# PineWoodDerby-Mega_Shield.net
KiCad netlist of a schematic drawn in EAGLE
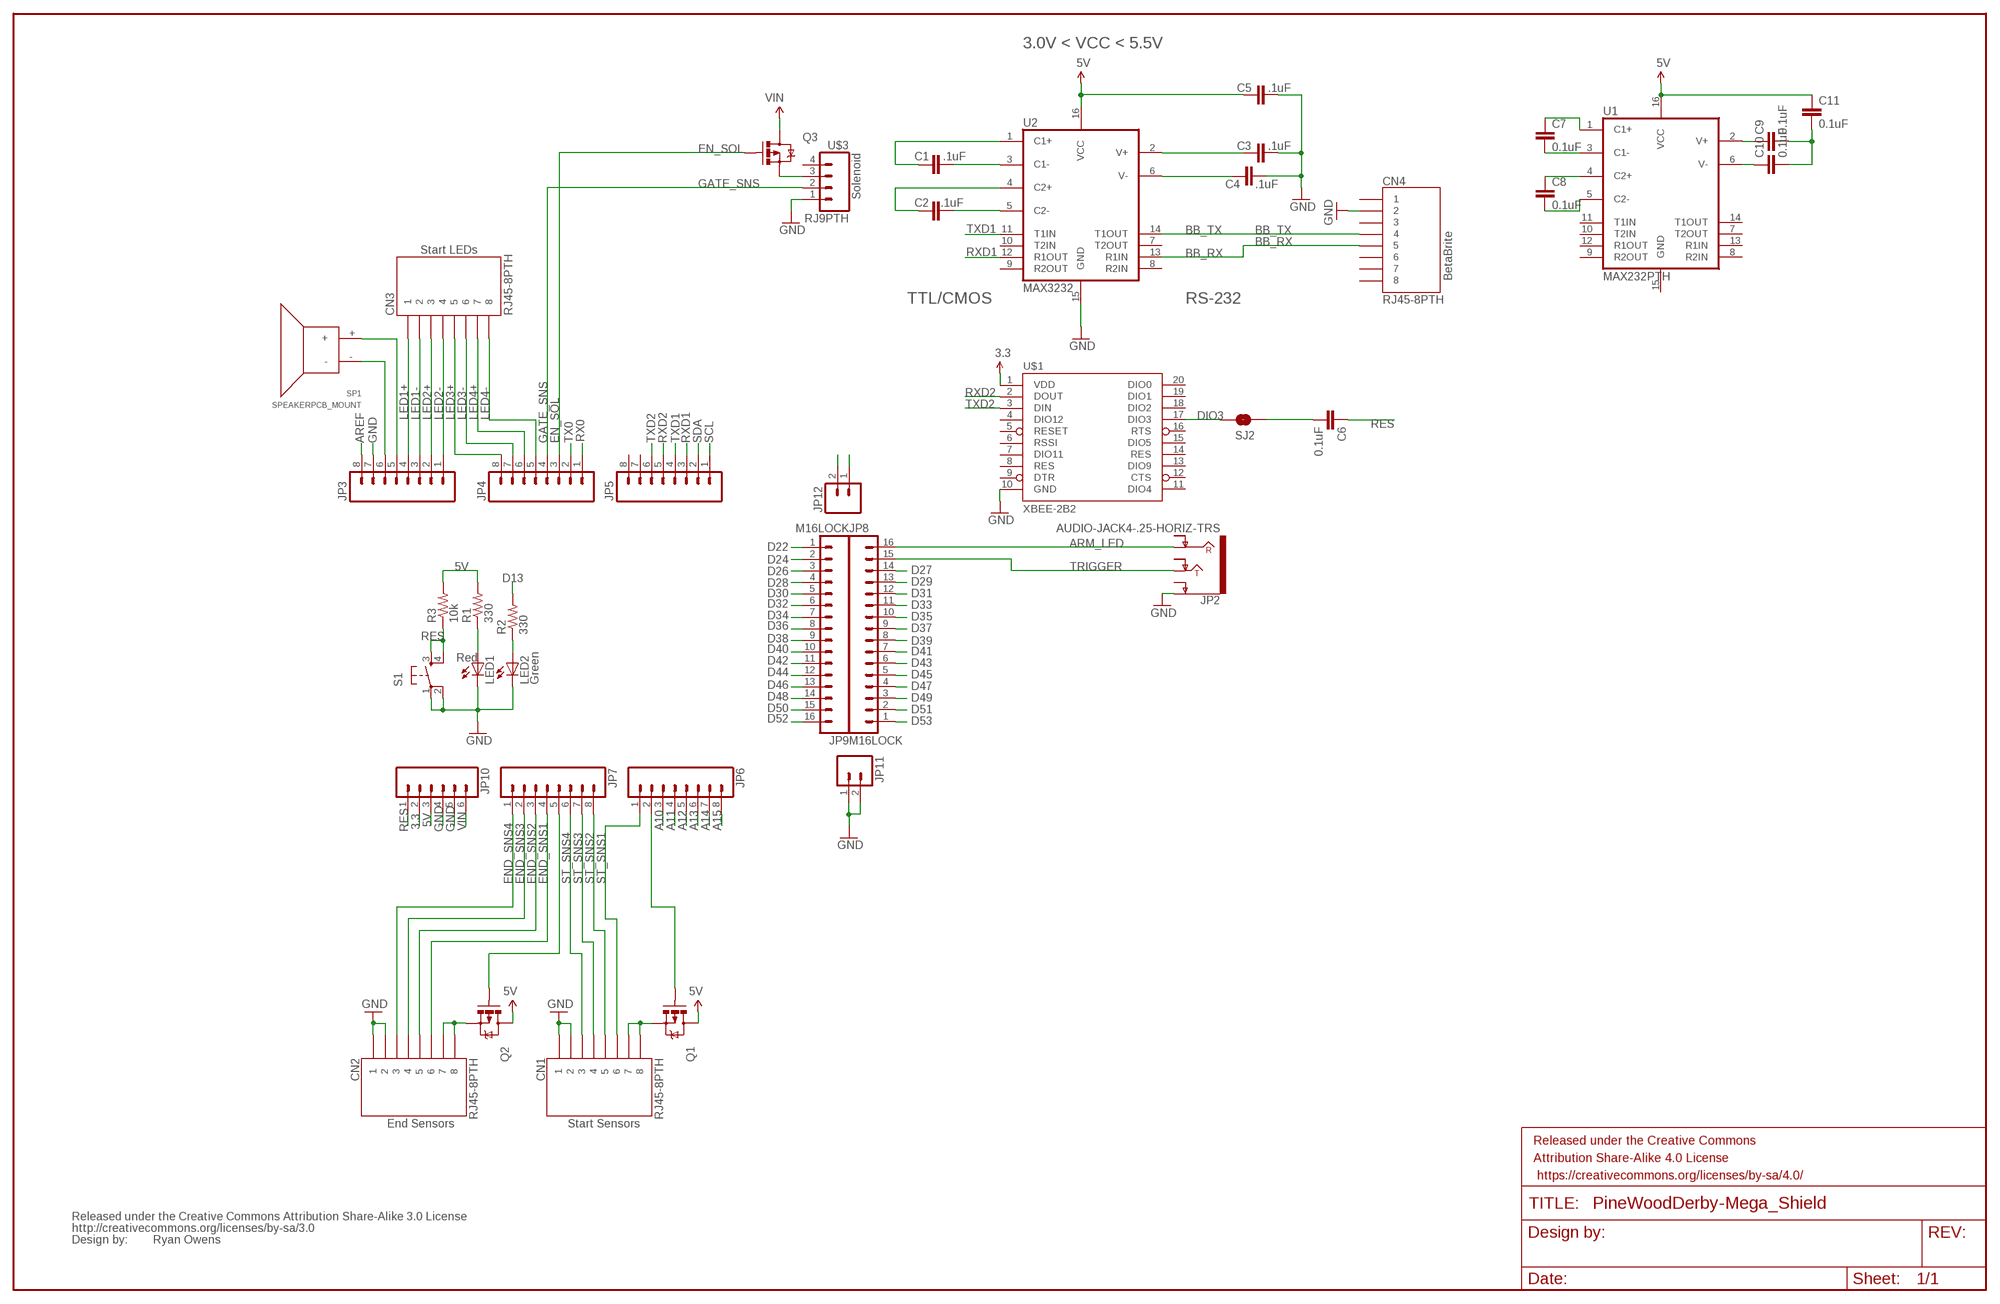
[diagram p0: schematic, sheet 1]

(export (version "E")
  (design (tool "Eeschema 10.0.6"))
  (components
    (comp (ref "C1")
      (value ".1uF")
      (footprint "eagle-import:0402-CAP")
      (libsource (lib "eagle-import") (part "SparkFun-Passives_CAP0402-CAP"))
    )
    (comp (ref "C2")
      (value ".1uF")
      (footprint "eagle-import:0402-CAP")
      (libsource (lib "eagle-import") (part "SparkFun-Passives_CAP0402-CAP"))
    )
    (comp (ref "C3")
      (value ".1uF")
      (footprint "eagle-import:0402-CAP")
      (libsource (lib "eagle-import") (part "SparkFun-Passives_CAP0402-CAP"))
    )
    (comp (ref "C4")
      (value ".1uF")
      (footprint "eagle-import:0402-CAP")
      (libsource (lib "eagle-import") (part "SparkFun-Passives_CAP0402-CAP"))
    )
    (comp (ref "C5")
      (value ".1uF")
      (footprint "eagle-import:0402-CAP")
      (libsource (lib "eagle-import") (part "SparkFun-Passives_CAP0402-CAP"))
    )
    (comp (ref "C6")
      (value "0.1uF")
      (footprint "eagle-import:0402-CAP")
      (libsource (lib "eagle-import") (part "CAP0402-CAP"))
    )
    (comp (ref "C7")
      (value "0.1uF")
      (footprint "eagle-import:CAP-PTH-SMALL-KIT")
      (libsource (lib "eagle-import") (part "0.1UF-50V-20%(PTH)KIT-EZ"))
    )
    (comp (ref "C8")
      (value "0.1uF")
      (footprint "eagle-import:CAP-PTH-SMALL-KIT")
      (libsource (lib "eagle-import") (part "0.1UF-50V-20%(PTH)KIT-EZ"))
    )
    (comp (ref "C9")
      (value "0.1uF")
      (footprint "eagle-import:CAP-PTH-SMALL-KIT")
      (libsource (lib "eagle-import") (part "0.1UF-50V-20%(PTH)KIT-EZ"))
    )
    (comp (ref "C10")
      (value "0.1uF")
      (footprint "eagle-import:CAP-PTH-SMALL-KIT")
      (libsource (lib "eagle-import") (part "0.1UF-50V-20%(PTH)KIT-EZ"))
    )
    (comp (ref "C11")
      (value "0.1uF")
      (footprint "eagle-import:CAP-PTH-SMALL-KIT")
      (libsource (lib "eagle-import") (part "0.1UF-50V-20%(PTH)KIT-EZ"))
    )
    (comp (ref "CN1")
      (value "RJ45-8PTH")
      (footprint "eagle-import:RJ45-8")
      (fields (field (name "LABEL") "Start Sensors"))
      (libsource (lib "eagle-import") (part "RJ45-8PTH"))
    )
    (comp (ref "CN2")
      (value "RJ45-8PTH")
      (footprint "eagle-import:RJ45-8")
      (fields (field (name "LABEL") "End Sensors"))
      (libsource (lib "eagle-import") (part "RJ45-8PTH"))
    )
    (comp (ref "CN3")
      (value "RJ45-8PTH")
      (footprint "eagle-import:RJ45-8")
      (fields (field (name "LABEL") "Start LEDs"))
      (libsource (lib "eagle-import") (part "RJ45-8PTH"))
    )
    (comp (ref "CN4")
      (value "RJ45-8PTH")
      (footprint "eagle-import:RJ45-8")
      (fields (field (name "LABEL") "BetaBrite"))
      (libsource (lib "eagle-import") (part "RJ45-8PTH"))
    )
    (comp (ref "FRAME2")
      (value "FRAME-LEDGER")
      (footprint "eagle-import:CREATIVE_COMMONS")
      (libsource (lib "eagle-import") (part "FRAME-LEDGER"))
    )
    (comp (ref "JP2")
      (value "AUDIO-JACK4-.25-HORIZ-TRS")
      (footprint "eagle-import:AUDIO-JACK-.25-INCH-HORIZ-PTH")
      (libsource (lib "eagle-import") (part "AUDIO-JACK4-.25-HORIZ-TRS"))
    )
    (comp (ref "JP3")
      (value "M08LOCK")
      (footprint "eagle-import:1X08_LOCK")
      (libsource (lib "eagle-import") (part "M08LOCK"))
    )
    (comp (ref "JP4")
      (value "M08LOCK")
      (footprint "eagle-import:1X08_LOCK")
      (libsource (lib "eagle-import") (part "M08LOCK"))
    )
    (comp (ref "JP5")
      (value "M08LOCK")
      (footprint "eagle-import:1X08_LOCK")
      (libsource (lib "eagle-import") (part "M08LOCK"))
    )
    (comp (ref "JP6")
      (value "M08LOCK")
      (footprint "eagle-import:1X08_LOCK")
      (libsource (lib "eagle-import") (part "M08LOCK"))
    )
    (comp (ref "JP7")
      (value "M08LOCK")
      (footprint "eagle-import:1X08_LOCK")
      (libsource (lib "eagle-import") (part "M08LOCK"))
    )
    (comp (ref "JP8")
      (value "M16LOCK")
      (footprint "eagle-import:1X16_LOCK")
      (libsource (lib "eagle-import") (part "M16LOCK"))
    )
    (comp (ref "JP9")
      (value "M16LOCK")
      (footprint "eagle-import:1X16_LOCK")
      (libsource (lib "eagle-import") (part "M16LOCK"))
    )
    (comp (ref "JP10")
      (value "M06LOCK")
      (footprint "eagle-import:1X06_LOCK")
      (libsource (lib "eagle-import") (part "M06LOCK"))
    )
    (comp (ref "JP11")
      (value "M02LOCK")
      (footprint "eagle-import:1X02_LOCK")
      (libsource (lib "eagle-import") (part "M02LOCK"))
    )
    (comp (ref "JP12")
      (value "M02LOCK")
      (footprint "eagle-import:1X02_LOCK")
      (libsource (lib "eagle-import") (part "M02LOCK"))
    )
    (comp (ref "LED1")
      (value "Red")
      (footprint "eagle-import:LED5MM")
      (libsource (lib "eagle-import") (part "LED5MM"))
    )
    (comp (ref "LED2")
      (value "Green")
      (footprint "eagle-import:LED5MM")
      (libsource (lib "eagle-import") (part "LED5MM"))
    )
    (comp (ref "Q1")
      (value "MOSFET-PCHANNELFQP27P06")
      (footprint "eagle-import:TO220V")
      (libsource (lib "eagle-import") (part "MOSFET-PCHANNELFQP27P06"))
    )
    (comp (ref "Q2")
      (value "MOSFET-PCHANNELFQP27P06")
      (footprint "eagle-import:TO220V")
      (libsource (lib "eagle-import") (part "MOSFET-PCHANNELFQP27P06"))
    )
    (comp (ref "Q3")
      (value "MOSFET-PCHANNELFQP27P06")
      (footprint "eagle-import:TO220V")
      (libsource (lib "eagle-import") (part "MOSFET-PCHANNELFQP27P06"))
    )
    (comp (ref "R1")
      (value "330")
      (footprint "eagle-import:AXIAL-0.3")
      (libsource (lib "eagle-import") (part "RESISTORPTH1"))
    )
    (comp (ref "R2")
      (value "330")
      (footprint "eagle-import:AXIAL-0.3")
      (libsource (lib "eagle-import") (part "RESISTORPTH1"))
    )
    (comp (ref "R3")
      (value "10k")
      (footprint "eagle-import:AXIAL-0.3")
      (libsource (lib "eagle-import") (part "RESISTORPTH1"))
    )
    (comp (ref "S1")
      (value "TAC_SWITCHPTH")
      (footprint "eagle-import:TACTILE-PTH")
      (libsource (lib "eagle-import") (part "TAC_SWITCHPTH"))
    )
    (comp (ref "SJ2")
      (value "SOLDERJUMPERTRACE")
      (footprint "eagle-import:SJ_2S-TRACE")
      (libsource (lib "eagle-import") (part "SOLDERJUMPERTRACE"))
    )
    (comp (ref "SP1")
      (value "SPEAKERPCB_MOUNT")
      (footprint "eagle-import:PCB_MOUNT_SPEAKER")
      (fields (field (name "MFG") "SANCO"))
      (libsource (lib "eagle-import") (part "SPEAKERPCB_MOUNT"))
    )
    (comp (ref "U$1")
      (value "XBEE-2B2")
      (footprint "eagle-import:XBEE-SILK")
      (libsource (lib "eagle-import") (part "XBEE-2B2"))
    )
    (comp (ref "U$2")
      (value "CREATIVE_COMMONS")
      (footprint "eagle-import:CREATIVE_COMMONS")
      (libsource (lib "eagle-import") (part "CREATIVE_COMMONS"))
    )
    (comp (ref "U$3")
      (value "RJ9PTH")
      (footprint "eagle-import:RJ9")
      (fields (field (name "LABEL") "Solenoid"))
      (libsource (lib "eagle-import") (part "RJ9PTH"))
    )
    (comp (ref "U1")
      (value "MAX232PTH")
      (footprint "eagle-import:DIL16")
      (libsource (lib "eagle-import") (part "MAX232PTH"))
    )
    (comp (ref "U2")
      (value "MAX3232")
      (footprint "eagle-import:SO016")
      (fields (field (name "PROD_ID") "IC-08171"))
      (libsource (lib "eagle-import") (part "MAX232SOIC16"))
    )
  )
  (nets
    (net (code "1") (name "/5V@1") (class "Default")
      (node (ref "JP12") (pin "1") (pinfunction "1_1") (pintype "passive"))
      (node (ref "JP12") (pin "2") (pinfunction "2_2") (pintype "passive"))
    )
    (net (code "2") (name "/A10") (class "Default")
      (node (ref "JP6") (pin "3") (pinfunction "3_3") (pintype "passive"))
    )
    (net (code "3") (name "/A11") (class "Default")
      (node (ref "JP6") (pin "4") (pinfunction "4_4") (pintype "passive"))
    )
    (net (code "4") (name "/A12") (class "Default")
      (node (ref "JP6") (pin "5") (pinfunction "5_5") (pintype "passive"))
    )
    (net (code "5") (name "/A13") (class "Default")
      (node (ref "JP6") (pin "6") (pinfunction "6_6") (pintype "passive"))
    )
    (net (code "6") (name "/A14") (class "Default")
      (node (ref "JP6") (pin "7") (pinfunction "7_7") (pintype "passive"))
    )
    (net (code "7") (name "/A15") (class "Default")
      (node (ref "JP6") (pin "8") (pinfunction "8_8") (pintype "passive"))
    )
    (net (code "8") (name "/AREF") (class "Default")
      (node (ref "JP3") (pin "8") (pinfunction "8_8") (pintype "passive"))
    )
    (net (code "9") (name "/ARM_LED") (class "Default")
      (node (ref "JP2") (pin "RING") (pinfunction "RING_RING") (pintype "bidirectional"))
      (node (ref "JP8") (pin "16") (pinfunction "16_16") (pintype "passive"))
    )
    (net (code "10") (name "/BB_RX") (class "Default")
      (node (ref "CN4") (pin "5") (pinfunction "5_5") (pintype "bidirectional"))
      (node (ref "U2") (pin "13") (pinfunction "R1IN_13") (pintype "input"))
    )
    (net (code "11") (name "/BB_TX") (class "Default")
      (node (ref "CN4") (pin "4") (pinfunction "4_4") (pintype "bidirectional"))
      (node (ref "U2") (pin "14") (pinfunction "T1OUT_14") (pintype "output"))
    )
    (net (code "12") (name "/D13") (class "Default")
      (node (ref "R2") (pin "P$2") (pinfunction "2_P$2") (pintype "passive"))
    )
    (net (code "13") (name "/D22") (class "Default")
      (node (ref "JP9") (pin "1") (pinfunction "1_1") (pintype "passive"))
    )
    (net (code "14") (name "/D24") (class "Default")
      (node (ref "JP9") (pin "2") (pinfunction "2_2") (pintype "passive"))
    )
    (net (code "15") (name "/D26") (class "Default")
      (node (ref "JP9") (pin "3") (pinfunction "3_3") (pintype "passive"))
    )
    (net (code "16") (name "/D27") (class "Default")
      (node (ref "JP8") (pin "14") (pinfunction "14_14") (pintype "passive"))
    )
    (net (code "17") (name "/D28") (class "Default")
      (node (ref "JP9") (pin "4") (pinfunction "4_4") (pintype "passive"))
    )
    (net (code "18") (name "/D29") (class "Default")
      (node (ref "JP8") (pin "13") (pinfunction "13_13") (pintype "passive"))
    )
    (net (code "19") (name "/D30") (class "Default")
      (node (ref "JP9") (pin "5") (pinfunction "5_5") (pintype "passive"))
    )
    (net (code "20") (name "/D31") (class "Default")
      (node (ref "JP8") (pin "12") (pinfunction "12_12") (pintype "passive"))
    )
    (net (code "21") (name "/D32") (class "Default")
      (node (ref "JP9") (pin "6") (pinfunction "6_6") (pintype "passive"))
    )
    (net (code "22") (name "/D33") (class "Default")
      (node (ref "JP8") (pin "11") (pinfunction "11_11") (pintype "passive"))
    )
    (net (code "23") (name "/D34") (class "Default")
      (node (ref "JP9") (pin "7") (pinfunction "7_7") (pintype "passive"))
    )
    (net (code "24") (name "/D35") (class "Default")
      (node (ref "JP8") (pin "10") (pinfunction "10_10") (pintype "passive"))
    )
    (net (code "25") (name "/D36") (class "Default")
      (node (ref "JP9") (pin "8") (pinfunction "8_8") (pintype "passive"))
    )
    (net (code "26") (name "/D37") (class "Default")
      (node (ref "JP8") (pin "9") (pinfunction "9_9") (pintype "passive"))
    )
    (net (code "27") (name "/D38") (class "Default")
      (node (ref "JP9") (pin "9") (pinfunction "9_9") (pintype "passive"))
    )
    (net (code "28") (name "/D39") (class "Default")
      (node (ref "JP8") (pin "8") (pinfunction "8_8") (pintype "passive"))
    )
    (net (code "29") (name "/D40") (class "Default")
      (node (ref "JP9") (pin "10") (pinfunction "10_10") (pintype "passive"))
    )
    (net (code "30") (name "/D41") (class "Default")
      (node (ref "JP8") (pin "7") (pinfunction "7_7") (pintype "passive"))
    )
    (net (code "31") (name "/D42") (class "Default")
      (node (ref "JP9") (pin "11") (pinfunction "11_11") (pintype "passive"))
    )
    (net (code "32") (name "/D43") (class "Default")
      (node (ref "JP8") (pin "6") (pinfunction "6_6") (pintype "passive"))
    )
    (net (code "33") (name "/D44") (class "Default")
      (node (ref "JP9") (pin "12") (pinfunction "12_12") (pintype "passive"))
    )
    (net (code "34") (name "/D45") (class "Default")
      (node (ref "JP8") (pin "5") (pinfunction "5_5") (pintype "passive"))
    )
    (net (code "35") (name "/D46") (class "Default")
      (node (ref "JP9") (pin "13") (pinfunction "13_13") (pintype "passive"))
    )
    (net (code "36") (name "/D47") (class "Default")
      (node (ref "JP8") (pin "4") (pinfunction "4_4") (pintype "passive"))
    )
    (net (code "37") (name "/D48") (class "Default")
      (node (ref "JP9") (pin "14") (pinfunction "14_14") (pintype "passive"))
    )
    (net (code "38") (name "/D49") (class "Default")
      (node (ref "JP8") (pin "3") (pinfunction "3_3") (pintype "passive"))
    )
    (net (code "39") (name "/D50") (class "Default")
      (node (ref "JP9") (pin "15") (pinfunction "15_15") (pintype "passive"))
    )
    (net (code "40") (name "/D51") (class "Default")
      (node (ref "JP8") (pin "2") (pinfunction "2_2") (pintype "passive"))
    )
    (net (code "41") (name "/D52") (class "Default")
      (node (ref "JP9") (pin "16") (pinfunction "16_16") (pintype "passive"))
    )
    (net (code "42") (name "/D53") (class "Default")
      (node (ref "JP8") (pin "1") (pinfunction "1_1") (pintype "passive"))
    )
    (net (code "43") (name "/DIO3") (class "Default")
      (node (ref "SJ2") (pin "2") (pinfunction "2_2") (pintype "passive"))
      (node (ref "U$1") (pin "17") (pinfunction "DIO3_17") (pintype "bidirectional"))
    )
    (net (code "44") (name "/END_SNS1") (class "Default")
      (node (ref "CN2") (pin "6") (pinfunction "6_6") (pintype "bidirectional"))
      (node (ref "JP7") (pin "4") (pinfunction "4_4") (pintype "passive"))
    )
    (net (code "45") (name "/END_SNS2") (class "Default")
      (node (ref "CN2") (pin "5") (pinfunction "5_5") (pintype "bidirectional"))
      (node (ref "JP7") (pin "3") (pinfunction "3_3") (pintype "passive"))
    )
    (net (code "46") (name "/END_SNS3") (class "Default")
      (node (ref "CN2") (pin "4") (pinfunction "4_4") (pintype "bidirectional"))
      (node (ref "JP7") (pin "2") (pinfunction "2_2") (pintype "passive"))
    )
    (net (code "47") (name "/END_SNS4") (class "Default")
      (node (ref "CN2") (pin "3") (pinfunction "3_3") (pintype "bidirectional"))
      (node (ref "JP7") (pin "1") (pinfunction "1_1") (pintype "passive"))
    )
    (net (code "48") (name "/EN_SOL") (class "Default")
      (node (ref "JP4") (pin "3") (pinfunction "3_3") (pintype "passive"))
      (node (ref "Q3") (pin "1") (pinfunction "G_1") (pintype "passive"))
    )
    (net (code "49") (name "/GATE_SNS") (class "Default")
      (node (ref "JP4") (pin "4") (pinfunction "4_4") (pintype "passive"))
      (node (ref "U$3") (pin "2") (pinfunction "2_2") (pintype "passive"))
    )
    (net (code "50") (name "/LED1+") (class "Default")
      (node (ref "CN3") (pin "1") (pinfunction "1_1") (pintype "bidirectional"))
      (node (ref "JP3") (pin "4") (pinfunction "4_4") (pintype "passive"))
    )
    (net (code "51") (name "/LED1-") (class "Default")
      (node (ref "CN3") (pin "2") (pinfunction "2_2") (pintype "bidirectional"))
      (node (ref "JP3") (pin "3") (pinfunction "3_3") (pintype "passive"))
    )
    (net (code "52") (name "/LED2+") (class "Default")
      (node (ref "CN3") (pin "3") (pinfunction "3_3") (pintype "bidirectional"))
      (node (ref "JP3") (pin "2") (pinfunction "2_2") (pintype "passive"))
    )
    (net (code "53") (name "/LED2-") (class "Default")
      (node (ref "CN3") (pin "4") (pinfunction "4_4") (pintype "bidirectional"))
      (node (ref "JP3") (pin "1") (pinfunction "1_1") (pintype "passive"))
    )
    (net (code "54") (name "/LED3+") (class "Default")
      (node (ref "CN3") (pin "5") (pinfunction "5_5") (pintype "bidirectional"))
      (node (ref "JP4") (pin "8") (pinfunction "8_8") (pintype "passive"))
    )
    (net (code "55") (name "/LED3-") (class "Default")
      (node (ref "CN3") (pin "6") (pinfunction "6_6") (pintype "bidirectional"))
      (node (ref "JP4") (pin "7") (pinfunction "7_7") (pintype "passive"))
    )
    (net (code "56") (name "/LED4+") (class "Default")
      (node (ref "CN3") (pin "7") (pinfunction "7_7") (pintype "bidirectional"))
      (node (ref "JP4") (pin "6") (pinfunction "6_6") (pintype "passive"))
    )
    (net (code "57") (name "/LED4-") (class "Default")
      (node (ref "CN3") (pin "8") (pinfunction "8_8") (pintype "bidirectional"))
      (node (ref "JP4") (pin "5") (pinfunction "5_5") (pintype "passive"))
    )
    (net (code "58") (name "/RES") (class "Default")
      (node (ref "C6") (pin "1") (pinfunction "1_1") (pintype "passive"))
      (node (ref "JP10") (pin "1") (pinfunction "1_1") (pintype "passive"))
      (node (ref "R3") (pin "P$1") (pinfunction "1_P$1") (pintype "passive"))
      (node (ref "S1") (pin "3") (pinfunction "3_3") (pintype "passive"))
      (node (ref "S1") (pin "4") (pinfunction "4_4") (pintype "passive"))
    )
    (net (code "59") (name "/RX0") (class "Default")
      (node (ref "JP4") (pin "1") (pinfunction "1_1") (pintype "passive"))
    )
    (net (code "60") (name "/RXD1") (class "Default")
      (node (ref "JP5") (pin "3") (pinfunction "3_3") (pintype "passive"))
      (node (ref "U2") (pin "12") (pinfunction "R1OUT_12") (pintype "output"))
    )
    (net (code "61") (name "/RXD2") (class "Default")
      (node (ref "JP5") (pin "5") (pinfunction "5_5") (pintype "passive"))
      (node (ref "U$1") (pin "2") (pinfunction "DOUT_2") (pintype "output"))
    )
    (net (code "62") (name "/SCL") (class "Default")
      (node (ref "JP5") (pin "1") (pinfunction "1_1") (pintype "passive"))
    )
    (net (code "63") (name "/SDA") (class "Default")
      (node (ref "JP5") (pin "2") (pinfunction "2_2") (pintype "passive"))
    )
    (net (code "64") (name "/ST_SNS1") (class "Default")
      (node (ref "CN1") (pin "6") (pinfunction "6_6") (pintype "bidirectional"))
      (node (ref "JP6") (pin "1") (pinfunction "1_1") (pintype "passive"))
    )
    (net (code "65") (name "/ST_SNS2") (class "Default")
      (node (ref "CN1") (pin "5") (pinfunction "5_5") (pintype "bidirectional"))
      (node (ref "JP7") (pin "8") (pinfunction "8_8") (pintype "passive"))
    )
    (net (code "66") (name "/ST_SNS3") (class "Default")
      (node (ref "CN1") (pin "4") (pinfunction "4_4") (pintype "bidirectional"))
      (node (ref "JP7") (pin "7") (pinfunction "7_7") (pintype "passive"))
    )
    (net (code "67") (name "/ST_SNS4") (class "Default")
      (node (ref "CN1") (pin "3") (pinfunction "3_3") (pintype "bidirectional"))
      (node (ref "JP7") (pin "6") (pinfunction "6_6") (pintype "passive"))
    )
    (net (code "68") (name "/TRIGGER") (class "Default")
      (node (ref "JP2") (pin "TIP") (pinfunction "TIP_TIP") (pintype "bidirectional"))
      (node (ref "JP8") (pin "15") (pinfunction "15_15") (pintype "passive"))
    )
    (net (code "69") (name "/TX0") (class "Default")
      (node (ref "JP4") (pin "2") (pinfunction "2_2") (pintype "passive"))
    )
    (net (code "70") (name "/TXD1") (class "Default")
      (node (ref "JP5") (pin "4") (pinfunction "4_4") (pintype "passive"))
      (node (ref "U2") (pin "11") (pinfunction "T1IN_11") (pintype "input"))
    )
    (net (code "71") (name "/TXD2") (class "Default")
      (node (ref "JP5") (pin "6") (pinfunction "6_6") (pintype "passive"))
      (node (ref "U$1") (pin "3") (pinfunction "DIN_3") (pintype "input"))
    )
    (net (code "72") (name "3.3") (class "Default")
      (node (ref "JP10") (pin "2") (pinfunction "2_2") (pintype "passive"))
      (node (ref "U$1") (pin "1") (pinfunction "VDD_1") (pintype "power_in"))
    )
    (net (code "73") (name "5V") (class "Default")
      (node (ref "C11") (pin "1") (pinfunction "1_1") (pintype "passive"))
      (node (ref "C5") (pin "1") (pinfunction "1_1") (pintype "passive"))
      (node (ref "JP10") (pin "3") (pinfunction "3_3") (pintype "passive"))
      (node (ref "Q1") (pin "2") (pinfunction "D_2") (pintype "passive"))
      (node (ref "Q2") (pin "2") (pinfunction "D_2") (pintype "passive"))
      (node (ref "R1") (pin "P$2") (pinfunction "2_P$2") (pintype "passive"))
      (node (ref "R3") (pin "P$2") (pinfunction "2_P$2") (pintype "passive"))
      (node (ref "U1") (pin "16") (pinfunction "VCC_16") (pintype "bidirectional"))
      (node (ref "U2") (pin "16") (pinfunction "VCC_16") (pintype "bidirectional"))
    )
    (net (code "74") (name "GND") (class "Default")
      (node (ref "C3") (pin "2") (pinfunction "2_2") (pintype "passive"))
      (node (ref "C4") (pin "2") (pinfunction "2_2") (pintype "passive"))
      (node (ref "C5") (pin "2") (pinfunction "2_2") (pintype "passive"))
      (node (ref "CN1") (pin "1") (pinfunction "1_1") (pintype "bidirectional"))
      (node (ref "CN1") (pin "2") (pinfunction "2_2") (pintype "bidirectional"))
      (node (ref "CN2") (pin "1") (pinfunction "1_1") (pintype "bidirectional"))
      (node (ref "CN2") (pin "2") (pinfunction "2_2") (pintype "bidirectional"))
      (node (ref "CN4") (pin "2") (pinfunction "2_2") (pintype "bidirectional"))
      (node (ref "JP10") (pin "4") (pinfunction "4_4") (pintype "passive"))
      (node (ref "JP10") (pin "5") (pinfunction "5_5") (pintype "passive"))
      (node (ref "JP11") (pin "1") (pinfunction "1_1") (pintype "passive"))
      (node (ref "JP11") (pin "2") (pinfunction "2_2") (pintype "passive"))
      (node (ref "JP2") (pin "SLEEVE") (pinfunction "EARTH_SLEEVE") (pintype "bidirectional"))
      (node (ref "JP3") (pin "7") (pinfunction "7_7") (pintype "passive"))
      (node (ref "LED1") (pin "K") (pinfunction "C_K") (pintype "passive"))
      (node (ref "LED2") (pin "K") (pinfunction "C_K") (pintype "passive"))
      (node (ref "S1") (pin "1") (pinfunction "1_1") (pintype "passive"))
      (node (ref "S1") (pin "2") (pinfunction "2_2") (pintype "passive"))
      (node (ref "U$1") (pin "10") (pinfunction "GND_10") (pintype "power_in"))
      (node (ref "U$3") (pin "1") (pinfunction "1_1") (pintype "passive"))
      (node (ref "U2") (pin "15") (pinfunction "GND_15") (pintype "bidirectional"))
    )
    (net (code "75") (name "Net-(C6-Pad2)") (class "Default")
      (node (ref "C6") (pin "2") (pinfunction "2_2") (pintype "passive"))
      (node (ref "SJ2") (pin "1") (pinfunction "1_1") (pintype "passive"))
    )
    (net (code "76") (name "Net-(C10-Pad2)") (class "Default")
      (node (ref "C10") (pin "2") (pinfunction "2_2") (pintype "passive"))
      (node (ref "C11") (pin "2") (pinfunction "2_2") (pintype "passive"))
      (node (ref "C9") (pin "2") (pinfunction "2_2") (pintype "passive"))
    )
    (net (code "77") (name "Net-(JP3-Pad5)") (class "Default")
      (node (ref "JP3") (pin "5") (pinfunction "5_5") (pintype "passive"))
      (node (ref "SP1") (pin "+") (pinfunction "+_+") (pintype "bidirectional"))
    )
    (net (code "78") (name "Net-(JP3-Pad6)") (class "Default")
      (node (ref "JP3") (pin "6") (pinfunction "6_6") (pintype "passive"))
      (node (ref "SP1") (pin "-") (pinfunction "-_-") (pintype "bidirectional"))
    )
    (net (code "79") (name "Net-(Q1-G)") (class "Default")
      (node (ref "JP6") (pin "2") (pinfunction "2_2") (pintype "passive"))
      (node (ref "Q1") (pin "1") (pinfunction "G_1") (pintype "passive"))
    )
    (net (code "80") (name "Net-(Q1-S)") (class "Default")
      (node (ref "CN1") (pin "7") (pinfunction "7_7") (pintype "bidirectional"))
      (node (ref "CN1") (pin "8") (pinfunction "8_8") (pintype "bidirectional"))
      (node (ref "Q1") (pin "3") (pinfunction "S_3") (pintype "passive"))
    )
    (net (code "81") (name "Net-(Q2-G)") (class "Default")
      (node (ref "JP7") (pin "5") (pinfunction "5_5") (pintype "passive"))
      (node (ref "Q2") (pin "1") (pinfunction "G_1") (pintype "passive"))
    )
    (net (code "82") (name "Net-(Q2-S)") (class "Default")
      (node (ref "CN2") (pin "7") (pinfunction "7_7") (pintype "bidirectional"))
      (node (ref "CN2") (pin "8") (pinfunction "8_8") (pintype "bidirectional"))
      (node (ref "Q2") (pin "3") (pinfunction "S_3") (pintype "passive"))
    )
    (net (code "83") (name "Net-(Q3-S)") (class "Default")
      (node (ref "Q3") (pin "3") (pinfunction "S_3") (pintype "passive"))
      (node (ref "U$3") (pin "3") (pinfunction "3_3") (pintype "passive"))
    )
    (net (code "84") (name "Net-(R1-1)") (class "Default")
      (node (ref "LED1") (pin "A") (pinfunction "A_A") (pintype "passive"))
      (node (ref "R1") (pin "P$1") (pinfunction "1_P$1") (pintype "passive"))
    )
    (net (code "85") (name "Net-(R2-1)") (class "Default")
      (node (ref "LED2") (pin "A") (pinfunction "A_A") (pintype "passive"))
      (node (ref "R2") (pin "P$1") (pinfunction "1_P$1") (pintype "passive"))
    )
    (net (code "86") (name "Net-(U1-C1+)") (class "Default")
      (node (ref "C7") (pin "1") (pinfunction "1_1") (pintype "passive"))
      (node (ref "U1") (pin "1") (pinfunction "C1+_1") (pintype "bidirectional"))
    )
    (net (code "87") (name "Net-(U1-C1-)") (class "Default")
      (node (ref "C7") (pin "2") (pinfunction "2_2") (pintype "passive"))
      (node (ref "U1") (pin "3") (pinfunction "C1-_3") (pintype "bidirectional"))
    )
    (net (code "88") (name "Net-(U1-C2+)") (class "Default")
      (node (ref "C8") (pin "1") (pinfunction "1_1") (pintype "passive"))
      (node (ref "U1") (pin "4") (pinfunction "C2+_4") (pintype "bidirectional"))
    )
    (net (code "89") (name "Net-(U1-C2-)") (class "Default")
      (node (ref "C8") (pin "2") (pinfunction "2_2") (pintype "passive"))
      (node (ref "U1") (pin "5") (pinfunction "C2-_5") (pintype "bidirectional"))
    )
    (net (code "90") (name "Net-(U1-V+)") (class "Default")
      (node (ref "C9") (pin "1") (pinfunction "1_1") (pintype "passive"))
      (node (ref "U1") (pin "2") (pinfunction "V+_2") (pintype "bidirectional"))
    )
    (net (code "91") (name "Net-(U1-V-)") (class "Default")
      (node (ref "C10") (pin "1") (pinfunction "1_1") (pintype "passive"))
      (node (ref "U1") (pin "6") (pinfunction "V-_6") (pintype "bidirectional"))
    )
    (net (code "92") (name "Net-(U2-C1+)") (class "Default")
      (node (ref "C1") (pin "1") (pinfunction "1_1") (pintype "passive"))
      (node (ref "U2") (pin "1") (pinfunction "C1+_1") (pintype "bidirectional"))
    )
    (net (code "93") (name "Net-(U2-C1-)") (class "Default")
      (node (ref "C1") (pin "2") (pinfunction "2_2") (pintype "passive"))
      (node (ref "U2") (pin "3") (pinfunction "C1-_3") (pintype "bidirectional"))
    )
    (net (code "94") (name "Net-(U2-C2+)") (class "Default")
      (node (ref "C2") (pin "1") (pinfunction "1_1") (pintype "passive"))
      (node (ref "U2") (pin "4") (pinfunction "C2+_4") (pintype "bidirectional"))
    )
    (net (code "95") (name "Net-(U2-C2-)") (class "Default")
      (node (ref "C2") (pin "2") (pinfunction "2_2") (pintype "passive"))
      (node (ref "U2") (pin "5") (pinfunction "C2-_5") (pintype "bidirectional"))
    )
    (net (code "96") (name "Net-(U2-V+)") (class "Default")
      (node (ref "C3") (pin "1") (pinfunction "1_1") (pintype "passive"))
      (node (ref "U2") (pin "2") (pinfunction "V+_2") (pintype "bidirectional"))
    )
    (net (code "97") (name "Net-(U2-V-)") (class "Default")
      (node (ref "C4") (pin "1") (pinfunction "1_1") (pintype "passive"))
      (node (ref "U2") (pin "6") (pinfunction "V-_6") (pintype "bidirectional"))
    )
    (net (code "98") (name "VIN") (class "Default")
      (node (ref "JP10") (pin "6") (pinfunction "6_6") (pintype "passive"))
      (node (ref "Q3") (pin "2") (pinfunction "D_2") (pintype "passive"))
    )
    (net (code "99") (name "unconnected-(CN4-Pad1)") (class "Default")
      (node (ref "CN4") (pin "1") (pinfunction "1_1") (pintype "bidirectional"))
    )
    (net (code "100") (name "unconnected-(CN4-Pad3)") (class "Default")
      (node (ref "CN4") (pin "3") (pinfunction "3_3") (pintype "bidirectional"))
    )
    (net (code "101") (name "unconnected-(CN4-Pad6)") (class "Default")
      (node (ref "CN4") (pin "6") (pinfunction "6_6") (pintype "bidirectional"))
    )
    (net (code "102") (name "unconnected-(CN4-Pad7)") (class "Default")
      (node (ref "CN4") (pin "7") (pinfunction "7_7") (pintype "bidirectional"))
    )
    (net (code "103") (name "unconnected-(CN4-Pad8)") (class "Default")
      (node (ref "CN4") (pin "8") (pinfunction "8_8") (pintype "bidirectional"))
    )
    (net (code "104") (name "unconnected-(JP2-EARTH-NORM-PadSLEEVE-NORM)") (class "Default")
      (node (ref "JP2") (pin "SLEEVE-NORM") (pinfunction "EARTH-NORM_SLEEVE-NORM") (pintype "bidirectional"))
    )
    (net (code "105") (name "unconnected-(JP2-PadRING-NORM)") (class "Default")
      (node (ref "JP2") (pin "RING-NORM") (pinfunction "RING-NORM_RING-NORM") (pintype "bidirectional"))
    )
    (net (code "106") (name "unconnected-(JP2-PadTIP-NORM)") (class "Default")
      (node (ref "JP2") (pin "TIP-NORM") (pinfunction "TIP-NORM_TIP-NORM") (pintype "bidirectional"))
    )
    (net (code "107") (name "unconnected-(JP5-Pad7)") (class "Default")
      (node (ref "JP5") (pin "7") (pinfunction "7_7") (pintype "passive"))
    )
    (net (code "108") (name "unconnected-(JP5-Pad8)") (class "Default")
      (node (ref "JP5") (pin "8") (pinfunction "8_8") (pintype "passive"))
    )
    (net (code "109") (name "unconnected-(U$1-CTS-Pad12)") (class "Default")
      (node (ref "U$1") (pin "12") (pinfunction "CTS_12") (pintype "output"))
    )
    (net (code "110") (name "unconnected-(U$1-DIO0-Pad20)") (class "Default")
      (node (ref "U$1") (pin "20") (pinfunction "DIO0_20") (pintype "bidirectional"))
    )
    (net (code "111") (name "unconnected-(U$1-DIO1-Pad19)") (class "Default")
      (node (ref "U$1") (pin "19") (pinfunction "DIO1_19") (pintype "bidirectional"))
    )
    (net (code "112") (name "unconnected-(U$1-DIO2-Pad18)") (class "Default")
      (node (ref "U$1") (pin "18") (pinfunction "DIO2_18") (pintype "bidirectional"))
    )
    (net (code "113") (name "unconnected-(U$1-DIO4-Pad11)") (class "Default")
      (node (ref "U$1") (pin "11") (pinfunction "DIO4_11") (pintype "bidirectional"))
    )
    (net (code "114") (name "unconnected-(U$1-DIO5-Pad15)") (class "Default")
      (node (ref "U$1") (pin "15") (pinfunction "DIO5_15") (pintype "bidirectional"))
    )
    (net (code "115") (name "unconnected-(U$1-DIO9-Pad13)") (class "Default")
      (node (ref "U$1") (pin "13") (pinfunction "DIO9_13") (pintype "bidirectional"))
    )
    (net (code "116") (name "unconnected-(U$1-DIO11-Pad7)") (class "Default")
      (node (ref "U$1") (pin "7") (pinfunction "DIO11_7") (pintype "bidirectional"))
    )
    (net (code "117") (name "unconnected-(U$1-DIO12-Pad4)") (class "Default")
      (node (ref "U$1") (pin "4") (pinfunction "DIO12_4") (pintype "bidirectional"))
    )
    (net (code "118") (name "unconnected-(U$1-DTR-Pad9)") (class "Default")
      (node (ref "U$1") (pin "9") (pinfunction "DTR_9") (pintype "bidirectional"))
    )
    (net (code "119") (name "unconnected-(U$1-RES-Pad8)") (class "Default")
      (node (ref "U$1") (pin "8") (pinfunction "RES_8") (pintype "bidirectional"))
    )
    (net (code "120") (name "unconnected-(U$1-RES-Pad14)") (class "Default")
      (node (ref "U$1") (pin "14") (pinfunction "RES_14") (pintype "bidirectional"))
    )
    (net (code "121") (name "unconnected-(U$1-RESET-Pad5)") (class "Default")
      (node (ref "U$1") (pin "5") (pinfunction "RESET_5") (pintype "input"))
    )
    (net (code "122") (name "unconnected-(U$1-RSSI-Pad6)") (class "Default")
      (node (ref "U$1") (pin "6") (pinfunction "RSSI_6") (pintype "bidirectional"))
    )
    (net (code "123") (name "unconnected-(U$1-RTS-Pad16)") (class "Default")
      (node (ref "U$1") (pin "16") (pinfunction "RTS_16") (pintype "input"))
    )
    (net (code "124") (name "unconnected-(U$3-Pad4)") (class "Default")
      (node (ref "U$3") (pin "4") (pinfunction "4_4") (pintype "passive"))
    )
    (net (code "125") (name "unconnected-(U1-GND-Pad15)") (class "Default")
      (node (ref "U1") (pin "15") (pinfunction "GND_15") (pintype "bidirectional"))
    )
    (net (code "126") (name "unconnected-(U1-R1IN-Pad13)") (class "Default")
      (node (ref "U1") (pin "13") (pinfunction "R1IN_13") (pintype "input"))
    )
    (net (code "127") (name "unconnected-(U1-R1OUT-Pad12)") (class "Default")
      (node (ref "U1") (pin "12") (pinfunction "R1OUT_12") (pintype "output"))
    )
    (net (code "128") (name "unconnected-(U1-R2IN-Pad8)") (class "Default")
      (node (ref "U1") (pin "8") (pinfunction "R2IN_8") (pintype "input"))
    )
    (net (code "129") (name "unconnected-(U1-R2OUT-Pad9)") (class "Default")
      (node (ref "U1") (pin "9") (pinfunction "R2OUT_9") (pintype "output"))
    )
    (net (code "130") (name "unconnected-(U1-T1IN-Pad11)") (class "Default")
      (node (ref "U1") (pin "11") (pinfunction "T1IN_11") (pintype "input"))
    )
    (net (code "131") (name "unconnected-(U1-T1OUT-Pad14)") (class "Default")
      (node (ref "U1") (pin "14") (pinfunction "T1OUT_14") (pintype "output"))
    )
    (net (code "132") (name "unconnected-(U1-T2IN-Pad10)") (class "Default")
      (node (ref "U1") (pin "10") (pinfunction "T2IN_10") (pintype "input"))
    )
    (net (code "133") (name "unconnected-(U1-T2OUT-Pad7)") (class "Default")
      (node (ref "U1") (pin "7") (pinfunction "T2OUT_7") (pintype "output"))
    )
    (net (code "134") (name "unconnected-(U2-R2IN-Pad8)") (class "Default")
      (node (ref "U2") (pin "8") (pinfunction "R2IN_8") (pintype "input"))
    )
    (net (code "135") (name "unconnected-(U2-R2OUT-Pad9)") (class "Default")
      (node (ref "U2") (pin "9") (pinfunction "R2OUT_9") (pintype "output"))
    )
    (net (code "136") (name "unconnected-(U2-T2IN-Pad10)") (class "Default")
      (node (ref "U2") (pin "10") (pinfunction "T2IN_10") (pintype "input"))
    )
    (net (code "137") (name "unconnected-(U2-T2OUT-Pad7)") (class "Default")
      (node (ref "U2") (pin "7") (pinfunction "T2OUT_7") (pintype "output"))
    )
  )
)
